# esp12f_all_pin.net
KiCad netlist of a schematic drawn in EAGLE
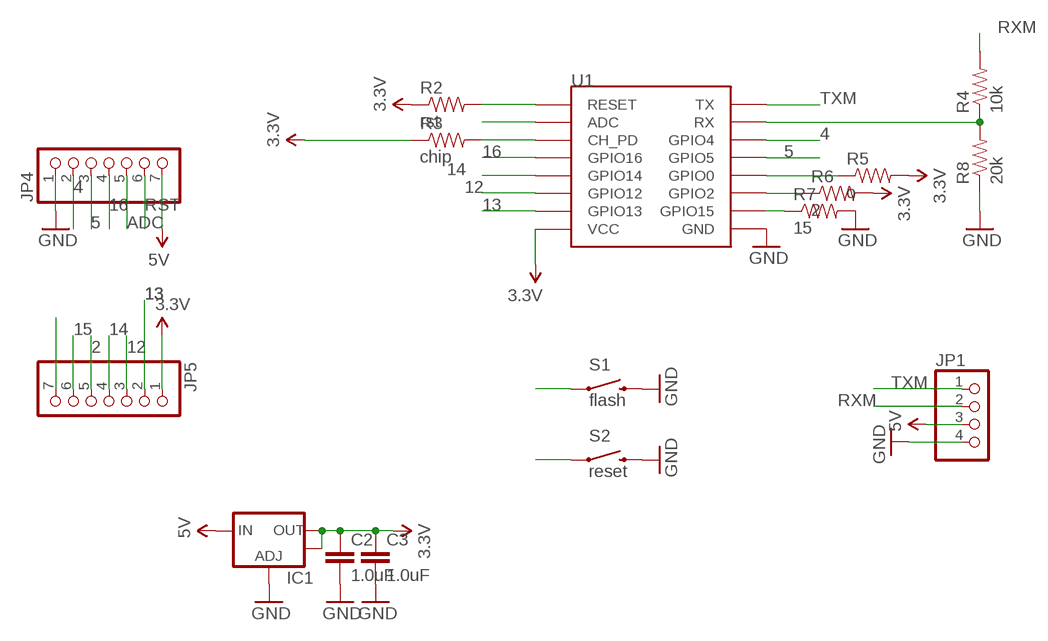
[diagram p0: schematic, sheet 1]

(export (version "E")
  (design (tool "Eeschema 10.0.6"))
  (components
    (comp (ref "C2")
      (value "1.0uF")
      (footprint "eagle-import:1206")
      (libsource (lib "eagle-import") (part "1.0UF50V10%(1206)"))
    )
    (comp (ref "C3")
      (value "1.0uF")
      (footprint "eagle-import:1206")
      (libsource (lib "eagle-import") (part "1.0UF50V10%(1206)"))
    )
    (comp (ref "IC1")
      (value "V_REG_LM1117SOT223")
      (footprint "eagle-import:SOT223")
      (libsource (lib "eagle-import") (part "V_REG_LM1117SOT223"))
    )
    (comp (ref "JP1")
      (value "PINHD-1X4")
      (footprint "eagle-import:1X04")
      (libsource (lib "eagle-import") (part "PINHD-1X4"))
    )
    (comp (ref "JP4")
      (value "PINHD-1X7")
      (footprint "eagle-import:1X07")
      (libsource (lib "eagle-import") (part "PINHD-1X7"))
    )
    (comp (ref "JP5")
      (value "PINHD-1X7")
      (footprint "eagle-import:1X07")
      (libsource (lib "eagle-import") (part "PINHD-1X7"))
    )
    (comp (ref "R2")
      (value "rst")
      (footprint "eagle-import:0805")
      (libsource (lib "eagle-import") (part "0.3OHM-1/8W-1%(0805)"))
    )
    (comp (ref "R3")
      (value "chip")
      (footprint "eagle-import:0805")
      (libsource (lib "eagle-import") (part "0.3OHM-1/8W-1%(0805)"))
    )
    (comp (ref "R4")
      (value "10k")
      (footprint "eagle-import:0805")
      (libsource (lib "eagle-import") (part "0.3OHM-1/8W-1%(0805)"))
    )
    (comp (ref "R5")
      (value "o")
      (footprint "eagle-import:0805")
      (libsource (lib "eagle-import") (part "0.3OHM-1/8W-1%(0805)"))
    )
    (comp (ref "R6")
      (value "2")
      (footprint "eagle-import:0805")
      (libsource (lib "eagle-import") (part "0.3OHM-1/8W-1%(0805)"))
    )
    (comp (ref "R7")
      (value "15")
      (footprint "eagle-import:0805")
      (libsource (lib "eagle-import") (part "0.3OHM-1/8W-1%(0805)"))
    )
    (comp (ref "R8")
      (value "20k")
      (footprint "eagle-import:0805")
      (libsource (lib "eagle-import") (part "0.3OHM-1/8W-1%(0805)"))
    )
    (comp (ref "S1")
      (value "flash")
      (footprint "eagle-import:TACTILE-SWITCH-1101NE")
      (libsource (lib "eagle-import") (part "SWITCH-MOMENTARY-2SMD-1101NE"))
    )
    (comp (ref "S2")
      (value "reset")
      (footprint "eagle-import:TACTILE-SWITCH-1101NE")
      (libsource (lib "eagle-import") (part "SWITCH-MOMENTARY-2SMD-1101NE"))
    )
    (comp (ref "U1")
      (value "ESP12SMD")
      (footprint "eagle-import:ESP12-SMD")
      (libsource (lib "eagle-import") (part "ESP12SMD"))
    )
  )
  (nets
    (net (code "1") (name "/0") (class "Default")
      (node (ref "JP5") (pin "7") (pinfunction "7_7") (pintype "passive"))
      (node (ref "R5") (pin "1") (pinfunction "1_1") (pintype "passive"))
      (node (ref "S1") (pin "1") (pinfunction "1_1") (pintype "passive"))
      (node (ref "U1") (pin "GPIO0") (pinfunction "GPIO0_GPIO0") (pintype "bidirectional"))
    )
    (net (code "2") (name "/2") (class "Default")
      (node (ref "JP5") (pin "5") (pinfunction "5_5") (pintype "passive"))
      (node (ref "R6") (pin "1") (pinfunction "1_1") (pintype "passive"))
      (node (ref "U1") (pin "GPIO2") (pinfunction "GPIO2_GPIO2") (pintype "bidirectional"))
    )
    (net (code "3") (name "/4") (class "Default")
      (node (ref "JP4") (pin "2") (pinfunction "2_2") (pintype "passive"))
      (node (ref "U1") (pin "GPIO4") (pinfunction "GPIO4_GPIO4") (pintype "bidirectional"))
    )
    (net (code "4") (name "/5") (class "Default")
      (node (ref "JP4") (pin "3") (pinfunction "3_3") (pintype "passive"))
      (node (ref "U1") (pin "GPIO5") (pinfunction "GPIO5_GPIO5") (pintype "bidirectional"))
    )
    (net (code "5") (name "/12") (class "Default")
      (node (ref "JP5") (pin "3") (pinfunction "3_3") (pintype "passive"))
      (node (ref "U1") (pin "GPIO12") (pinfunction "GPIO12_GPIO12") (pintype "bidirectional"))
    )
    (net (code "6") (name "/13") (class "Default")
      (node (ref "JP5") (pin "2") (pinfunction "2_2") (pintype "passive"))
      (node (ref "U1") (pin "GPIO13") (pinfunction "GPIO13_GPIO13") (pintype "bidirectional"))
    )
    (net (code "7") (name "/14") (class "Default")
      (node (ref "JP5") (pin "4") (pinfunction "4_4") (pintype "passive"))
      (node (ref "U1") (pin "GPIO14") (pinfunction "GPIO14_GPIO14") (pintype "bidirectional"))
    )
    (net (code "8") (name "/15") (class "Default")
      (node (ref "JP5") (pin "6") (pinfunction "6_6") (pintype "passive"))
      (node (ref "R7") (pin "1") (pinfunction "1_1") (pintype "passive"))
      (node (ref "U1") (pin "GPIO15") (pinfunction "GPIO15_GPIO15") (pintype "bidirectional"))
    )
    (net (code "9") (name "/16") (class "Default")
      (node (ref "JP4") (pin "4") (pinfunction "4_4") (pintype "passive"))
      (node (ref "U1") (pin "GPIO16") (pinfunction "GPIO16_GPIO16") (pintype "bidirectional"))
    )
    (net (code "10") (name "/ADC") (class "Default")
      (node (ref "JP4") (pin "5") (pinfunction "5_5") (pintype "passive"))
      (node (ref "U1") (pin "ADC") (pinfunction "ADC_ADC") (pintype "bidirectional"))
    )
    (net (code "11") (name "/RST") (class "Default")
      (node (ref "JP4") (pin "6") (pinfunction "6_6") (pintype "passive"))
      (node (ref "R2") (pin "2") (pinfunction "2_2") (pintype "passive"))
      (node (ref "S2") (pin "1") (pinfunction "1_1") (pintype "passive"))
      (node (ref "U1") (pin "RESET") (pinfunction "RESET_RESET") (pintype "bidirectional"))
    )
    (net (code "12") (name "/RXM") (class "Default")
      (node (ref "JP1") (pin "2") (pinfunction "2_2") (pintype "passive"))
      (node (ref "R4") (pin "2") (pinfunction "2_2") (pintype "passive"))
    )
    (net (code "13") (name "/TXM") (class "Default")
      (node (ref "JP1") (pin "1") (pinfunction "1_1") (pintype "passive"))
      (node (ref "U1") (pin "TXD0") (pinfunction "TX_TXD0") (pintype "bidirectional"))
    )
    (net (code "14") (name "3.3V") (class "Default")
      (node (ref "C2") (pin "1") (pinfunction "1_1") (pintype "passive"))
      (node (ref "C3") (pin "1") (pinfunction "1_1") (pintype "passive"))
      (node (ref "IC1") (pin "2") (pinfunction "OUT_2") (pintype "output"))
      (node (ref "IC1") (pin "4") (pinfunction "OUT_4") (pintype "output"))
      (node (ref "JP5") (pin "1") (pinfunction "1_1") (pintype "passive"))
      (node (ref "R2") (pin "1") (pinfunction "1_1") (pintype "passive"))
      (node (ref "R3") (pin "1") (pinfunction "1_1") (pintype "passive"))
      (node (ref "R5") (pin "2") (pinfunction "2_2") (pintype "passive"))
      (node (ref "R6") (pin "2") (pinfunction "2_2") (pintype "passive"))
      (node (ref "U1") (pin "VCC") (pinfunction "VCC_VCC") (pintype "bidirectional"))
    )
    (net (code "15") (name "5V") (class "Default")
      (node (ref "IC1") (pin "3") (pinfunction "IN_3") (pintype "input"))
      (node (ref "JP1") (pin "3") (pinfunction "3_3") (pintype "passive"))
      (node (ref "JP4") (pin "7") (pinfunction "7_7") (pintype "passive"))
    )
    (net (code "16") (name "GND") (class "Default")
      (node (ref "C2") (pin "2") (pinfunction "2_2") (pintype "passive"))
      (node (ref "C3") (pin "2") (pinfunction "2_2") (pintype "passive"))
      (node (ref "IC1") (pin "1") (pinfunction "ADJ_1") (pintype "input"))
      (node (ref "JP1") (pin "4") (pinfunction "4_4") (pintype "passive"))
      (node (ref "JP4") (pin "1") (pinfunction "1_1") (pintype "passive"))
      (node (ref "R7") (pin "2") (pinfunction "2_2") (pintype "passive"))
      (node (ref "R8") (pin "1") (pinfunction "1_1") (pintype "passive"))
      (node (ref "S1") (pin "2") (pinfunction "2_2") (pintype "passive"))
      (node (ref "S2") (pin "2") (pinfunction "2_2") (pintype "passive"))
      (node (ref "U1") (pin "GND") (pinfunction "GND_GND") (pintype "bidirectional"))
    )
    (net (code "17") (name "Net-(R3-Pad2)") (class "Default")
      (node (ref "R3") (pin "2") (pinfunction "2_2") (pintype "passive"))
      (node (ref "U1") (pin "CH_PD") (pinfunction "CH_PD_CH_PD") (pintype "bidirectional"))
    )
    (net (code "18") (name "Net-(U1-RX)") (class "Default")
      (node (ref "R4") (pin "1") (pinfunction "1_1") (pintype "passive"))
      (node (ref "R8") (pin "2") (pinfunction "2_2") (pintype "passive"))
      (node (ref "U1") (pin "RXD0") (pinfunction "RX_RXD0") (pintype "bidirectional"))
    )
  )
)
